# msp432-standard-feather.net
KiCad netlist of a schematic drawn in EAGLE
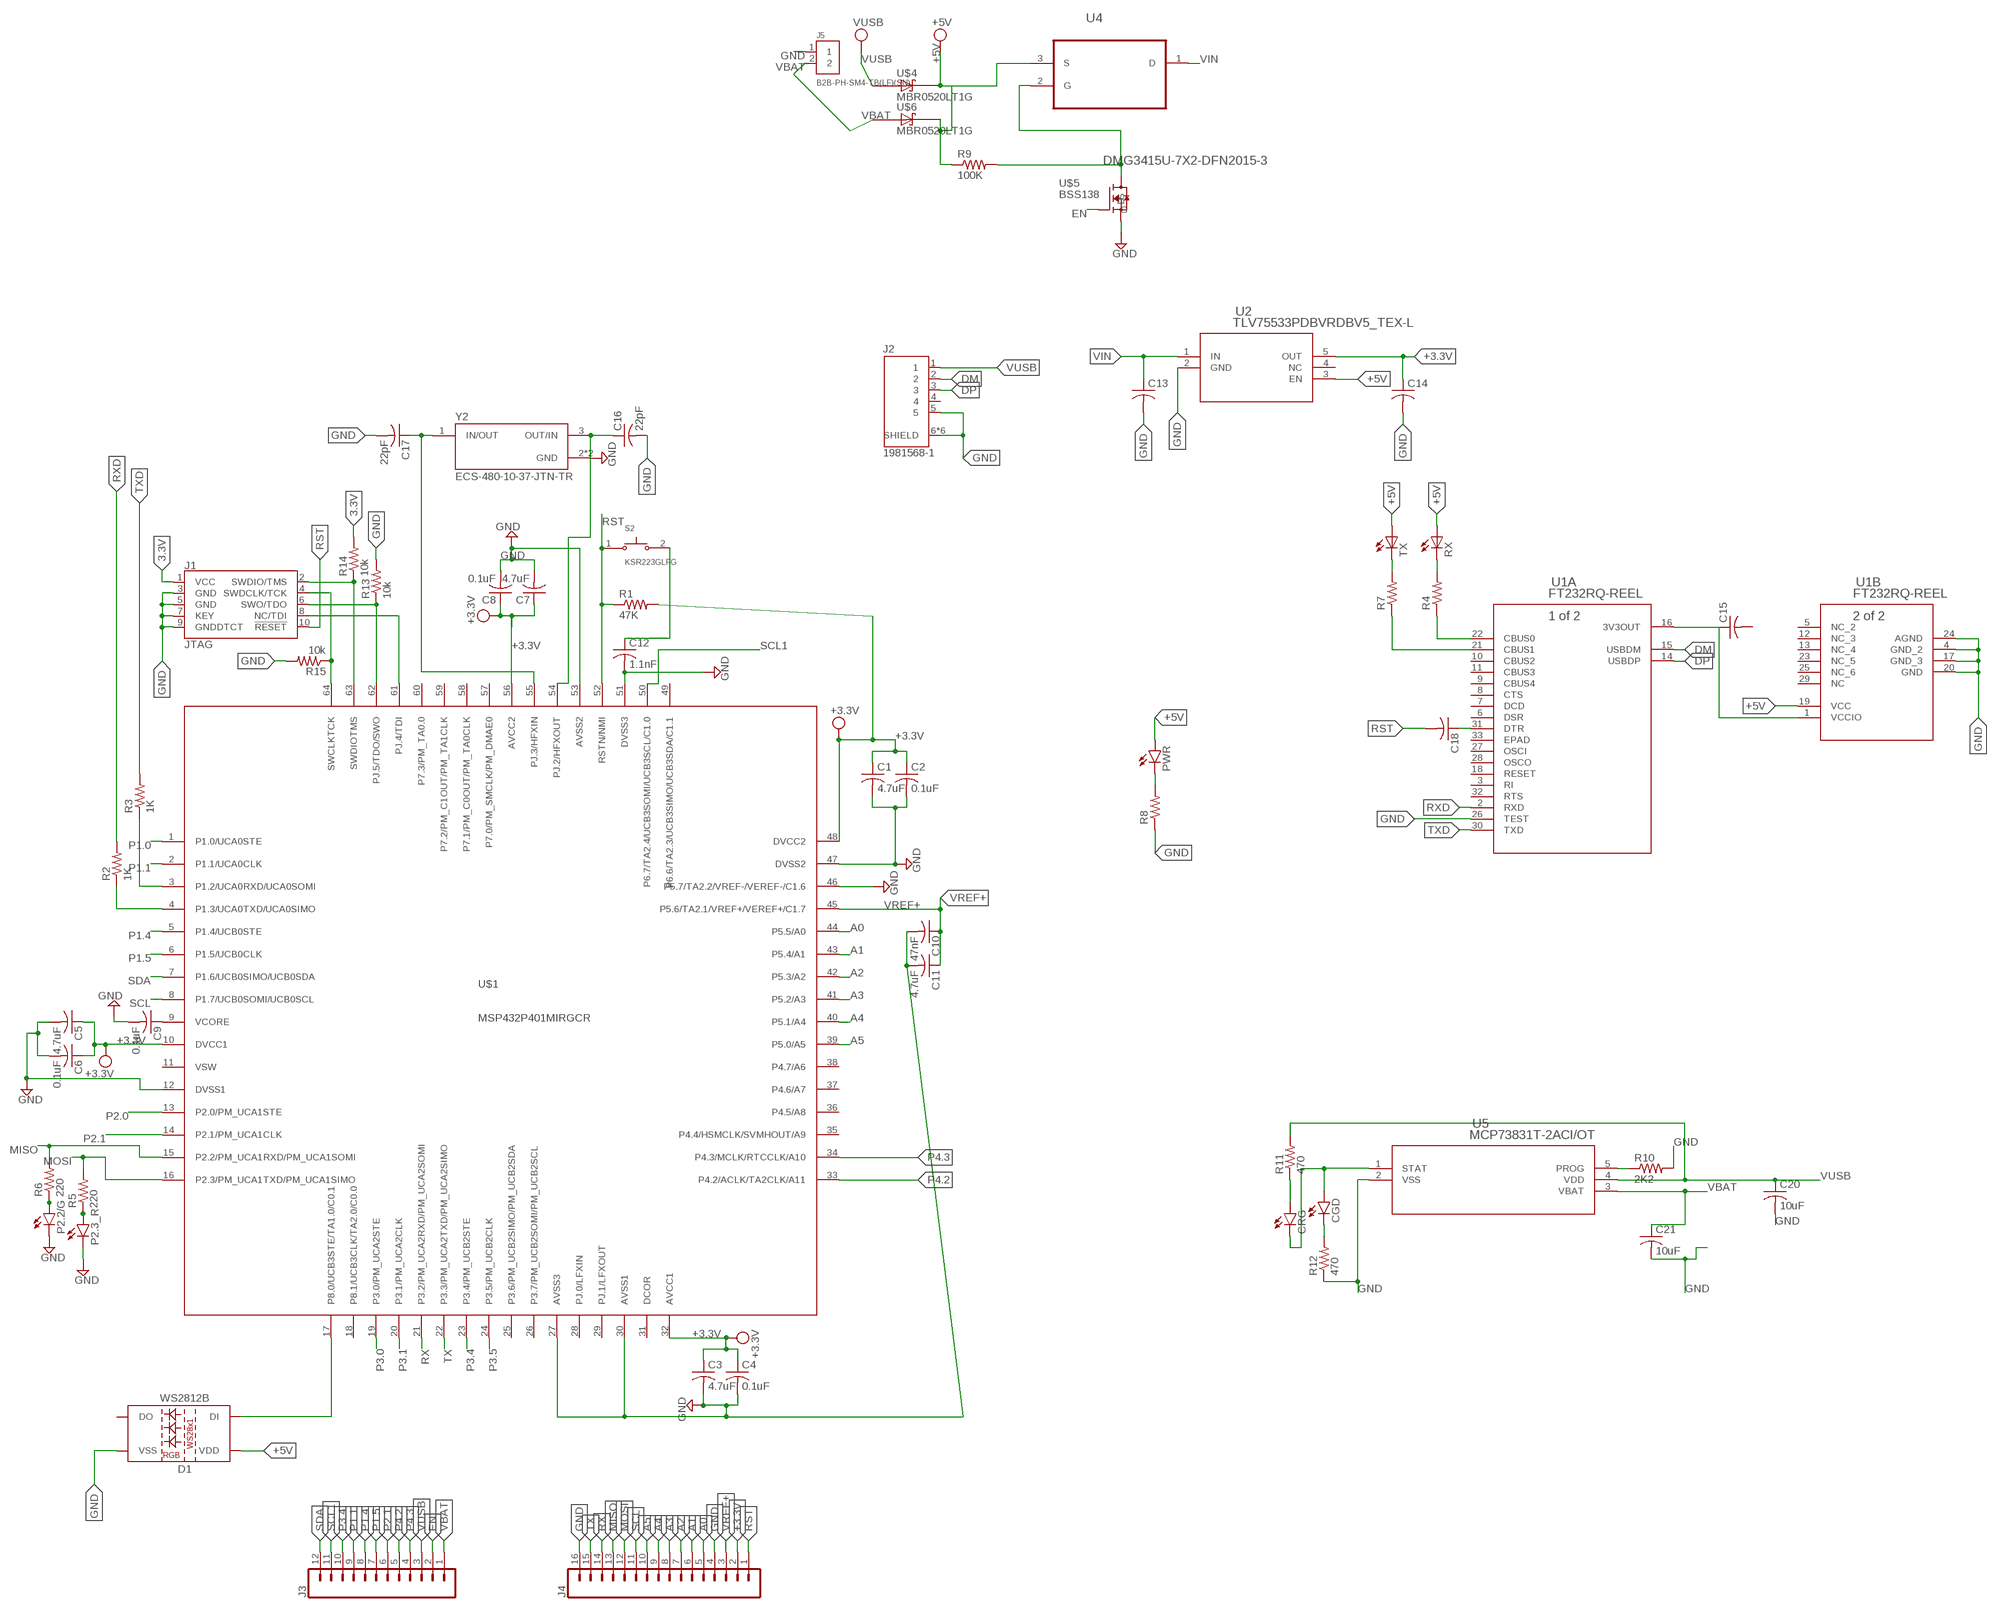
[diagram p0: schematic, sheet 1]

(export (version "E")
  (design (tool "Eeschema 10.0.6"))
  (components
    (comp (ref "C1")
      (value "4.7uF")
      (footprint "eagle-import:C0603")
      (libsource (lib "eagle-import") (part "C-USC0603"))
    )
    (comp (ref "C2")
      (value "0.1uF")
      (footprint "eagle-import:C0402")
      (libsource (lib "eagle-import") (part "C-USC0402"))
    )
    (comp (ref "C3")
      (value "4.7uF")
      (footprint "eagle-import:C0603")
      (libsource (lib "eagle-import") (part "C-USC0603"))
    )
    (comp (ref "C4")
      (value "0.1uF")
      (footprint "eagle-import:C0402")
      (libsource (lib "eagle-import") (part "C-USC0402"))
    )
    (comp (ref "C5")
      (value "4.7uF")
      (footprint "eagle-import:C0603")
      (libsource (lib "eagle-import") (part "C-USC0603"))
    )
    (comp (ref "C6")
      (value "0.1uF")
      (footprint "eagle-import:C0402")
      (libsource (lib "eagle-import") (part "C-USC0402"))
    )
    (comp (ref "C7")
      (value "4.7uF")
      (footprint "eagle-import:C0603")
      (libsource (lib "eagle-import") (part "C-USC0603"))
    )
    (comp (ref "C8")
      (value "0.1uF")
      (footprint "eagle-import:C0402")
      (libsource (lib "eagle-import") (part "C-USC0402"))
    )
    (comp (ref "C9")
      (value "0.1uF")
      (footprint "eagle-import:C0402")
      (libsource (lib "eagle-import") (part "C-USC0402"))
    )
    (comp (ref "C10")
      (value "47nF")
      (footprint "eagle-import:C0402")
      (libsource (lib "eagle-import") (part "C-USC0402"))
    )
    (comp (ref "C11")
      (value "4.7uF")
      (footprint "eagle-import:C0603")
      (libsource (lib "eagle-import") (part "C-USC0603"))
    )
    (comp (ref "C12")
      (value "1.1nF")
      (footprint "eagle-import:C0402")
      (libsource (lib "eagle-import") (part "C-USC0402"))
    )
    (comp (ref "C13")
      (value "C-USC0402")
      (footprint "eagle-import:C0402")
      (libsource (lib "eagle-import") (part "C-USC0402"))
    )
    (comp (ref "C14")
      (value "C-USC0402")
      (footprint "eagle-import:C0402")
      (libsource (lib "eagle-import") (part "C-USC0402"))
    )
    (comp (ref "C15")
      (value "C-USC0402")
      (footprint "eagle-import:C0402")
      (libsource (lib "eagle-import") (part "C-USC0402"))
    )
    (comp (ref "C16")
      (value "22pF")
      (footprint "eagle-import:C0402")
      (libsource (lib "eagle-import") (part "C-USC0402"))
    )
    (comp (ref "C17")
      (value "22pF")
      (footprint "eagle-import:C0402")
      (libsource (lib "eagle-import") (part "C-USC0402"))
    )
    (comp (ref "C18")
      (value "C-USC0402")
      (footprint "eagle-import:C0402")
      (libsource (lib "eagle-import") (part "C-USC0402"))
    )
    (comp (ref "C20")
      (value "10uF")
      (footprint "eagle-import:C0603")
      (libsource (lib "eagle-import") (part "C-USC0603"))
    )
    (comp (ref "C21")
      (value "10uF")
      (footprint "eagle-import:C0603")
      (libsource (lib "eagle-import") (part "C-USC0603"))
    )
    (comp (ref "CGD")
      (value "LEDCHIP-LED0603")
      (footprint "eagle-import:CHIP-LED0603")
      (libsource (lib "eagle-import") (part "led_259_LEDCHIP-LED0603"))
    )
    (comp (ref "CRG")
      (value "LEDCHIP-LED0603")
      (footprint "eagle-import:CHIP-LED0603")
      (libsource (lib "eagle-import") (part "led_259_LEDCHIP-LED0603"))
    )
    (comp (ref "D1")
      (value "WS2812B")
      (footprint "eagle-import:WS2812B")
      (libsource (lib "eagle-import") (part "WS2812B"))
    )
    (comp (ref "J1")
      (value "JTAG")
      (footprint "eagle-import:2X5-SMD-1.27MM")
      (libsource (lib "eagle-import") (part "CORTEX_JTAG_DEBUG_SMD"))
    )
    (comp (ref "J2")
      (value "1981568-1")
      (footprint "eagle-import:TE_1981568-1")
      (fields (field (name "MF") "TE Connectivity") (field (name "MP") "19815681"))
      (libsource (lib "eagle-import") (part "1981568-1"))
    )
    (comp (ref "J3")
      (value "CONN_12NO_SILK")
      (footprint "eagle-import:1X12_NO_SILK")
      (libsource (lib "eagle-import") (part "CONN_12NO_SILK"))
    )
    (comp (ref "J4")
      (value "CONN_161X16_NO_SILK")
      (footprint "eagle-import:1X16_NO_SILK")
      (libsource (lib "eagle-import") (part "CONN_161X16_NO_SILK"))
    )
    (comp (ref "J5")
      (value "B2B-PH-SM4-TB(LF)(SN)")
      (footprint "eagle-import:JST_B2B-PH-SM4-TB(LF)(SN)")
      (fields (field (name "MF") "JST Sales") (field (name "MP") "B2B-PH-SM4-TB_LF__SN_"))
      (libsource (lib "eagle-import") (part "B2B-PH-SM4-TB(LF)(SN)"))
    )
    (comp (ref "P2.2/G")
      (value "LEDCHIP-LED0603")
      (footprint "eagle-import:CHIP-LED0603")
      (libsource (lib "eagle-import") (part "led_259_LEDCHIP-LED0603"))
    )
    (comp (ref "P2.3_R")
      (value "LEDCHIP-LED0603")
      (footprint "eagle-import:CHIP-LED0603")
      (libsource (lib "eagle-import") (part "led_259_LEDCHIP-LED0603"))
    )
    (comp (ref "PWR")
      (value "LEDCHIP-LED0603")
      (footprint "eagle-import:CHIP-LED0603")
      (libsource (lib "eagle-import") (part "led_259_LEDCHIP-LED0603"))
    )
    (comp (ref "R1")
      (value "47K")
      (footprint "eagle-import:R0402")
      (libsource (lib "eagle-import") (part "R-US_R0402"))
    )
    (comp (ref "R2")
      (value "1K")
      (footprint "eagle-import:R0402")
      (libsource (lib "eagle-import") (part "R-US_R0402"))
    )
    (comp (ref "R3")
      (value "1K")
      (footprint "eagle-import:R0402")
      (libsource (lib "eagle-import") (part "R-US_R0402"))
    )
    (comp (ref "R4")
      (value "R-US_R0402")
      (footprint "eagle-import:R0402")
      (libsource (lib "eagle-import") (part "R-US_R0402"))
    )
    (comp (ref "R5")
      (value "220")
      (footprint "eagle-import:R0402")
      (libsource (lib "eagle-import") (part "R-US_R0402"))
    )
    (comp (ref "R6")
      (value "220")
      (footprint "eagle-import:R0402")
      (libsource (lib "eagle-import") (part "R-US_R0402"))
    )
    (comp (ref "R7")
      (value "R-US_R0402")
      (footprint "eagle-import:R0402")
      (libsource (lib "eagle-import") (part "R-US_R0402"))
    )
    (comp (ref "R8")
      (value "R-US_R0402")
      (footprint "eagle-import:R0402")
      (libsource (lib "eagle-import") (part "R-US_R0402"))
    )
    (comp (ref "R9")
      (value "100K")
      (footprint "eagle-import:R0402")
      (libsource (lib "eagle-import") (part "R-US_R0402"))
    )
    (comp (ref "R10")
      (value "2K2")
      (footprint "eagle-import:R0402")
      (libsource (lib "eagle-import") (part "R-US_R0402"))
    )
    (comp (ref "R11")
      (value "470")
      (footprint "eagle-import:R0402")
      (libsource (lib "eagle-import") (part "R-US_R0402"))
    )
    (comp (ref "R12")
      (value "470")
      (footprint "eagle-import:R0402")
      (libsource (lib "eagle-import") (part "R-US_R0402"))
    )
    (comp (ref "R13")
      (value "10k")
      (footprint "eagle-import:R0402")
      (libsource (lib "eagle-import") (part "R-US_R0402"))
    )
    (comp (ref "R14")
      (value "10k")
      (footprint "eagle-import:R0402")
      (libsource (lib "eagle-import") (part "R-US_R0402"))
    )
    (comp (ref "R15")
      (value "10k")
      (footprint "eagle-import:R0402")
      (libsource (lib "eagle-import") (part "R-US_R0402"))
    )
    (comp (ref "RX")
      (value "LEDCHIP-LED0603")
      (footprint "eagle-import:CHIP-LED0603")
      (libsource (lib "eagle-import") (part "LEDCHIP-LED0603"))
    )
    (comp (ref "S2")
      (value "KSR223GLFG")
      (footprint "eagle-import:SW_KSR223GLFG")
      (fields (field (name "MF") "C&K"))
      (libsource (lib "eagle-import") (part "KSR223GLFG"))
    )
    (comp (ref "TX")
      (value "LEDCHIP-LED0603")
      (footprint "eagle-import:CHIP-LED0603")
      (libsource (lib "eagle-import") (part "LEDCHIP-LED0603"))
    )
    (comp (ref "U$1")
      (value "MSP432P401MIRGCR")
      (footprint "eagle-import:MSP432_QFN_64")
      (fields (field (name "MF") "Texas Instruments"))
      (libsource (lib "eagle-import") (part "MSP432P401MIRGCR"))
    )
    (comp (ref "U$4")
      (value "MBR0520LT1G")
      (footprint "eagle-import:SOD3716X117(SOD-123)")
      (fields (field (name "MF") "ON Semiconductor"))
      (libsource (lib "eagle-import") (part "MBR0520LT1G"))
    )
    (comp (ref "U$5")
      (value "BSS138")
      (footprint "eagle-import:BSS138")
      (fields (field (name "MF") "MICROSS/On Semiconductor"))
      (libsource (lib "eagle-import") (part "BSS138"))
    )
    (comp (ref "U$6")
      (value "MBR0520LT1G")
      (footprint "eagle-import:SOD3716X117(SOD-123)")
      (fields (field (name "MF") "ON Semiconductor"))
      (libsource (lib "eagle-import") (part "MBR0520LT1G"))
    )
    (comp (ref "U1")
      (value "FT232RQ-REEL")
      (footprint "eagle-import:FT232RQ-REEL_FTD")
      (fields (field (name "COPYRIGHT") "Copyright (C) 2018 Accelerated Designs. All rights reserved"))
      (libsource (lib "eagle-import") (part "FT232RQ-REEL"))
    )
    (comp (ref "U2")
      (value "TLV75533PDBVRDBV5_TEX-L")
      (footprint "eagle-import:DBV5_TEX-L")
      (fields
        (field (name "MANUFACTURER_PART_NUMBER") "TLV75533PDBVR")
        (field (name "COPYRIGHT") "Copyright (C) 2018 Accelerated Designs. All rights reserved")
      )
      (libsource (lib "eagle-import") (part "TLV75533PDBVRDBV5_TEX-L"))
    )
    (comp (ref "U4")
      (value "DMG3415U-7X2-DFN2015-3")
      (footprint "eagle-import:X2-DFN2015-3")
      (libsource (lib "eagle-import") (part "DMG3415U-7X2-DFN2015-3"))
    )
    (comp (ref "U5")
      (value "MCP73831T-2ACI/OT")
      (footprint "eagle-import:SOT-23-5_MC")
      (libsource (lib "eagle-import") (part "MCP73831T-2ACI/OT"))
    )
    (comp (ref "Y2")
      (value "ECS-480-10-37-JTN-TR")
      (footprint "eagle-import:XTAL_ECS-480-10-37-JTN-TR")
      (fields (field (name "MF") "ECS Inc."))
      (libsource (lib "eagle-import") (part "ECS-480-10-37-JTN-TR"))
    )
  )
  (nets
    (net (code "1") (name "+3.3V") (class "Default")
      (node (ref "C1") (pin "1") (pinfunction "1_1") (pintype "passive"))
      (node (ref "C14") (pin "1") (pinfunction "1_1") (pintype "passive"))
      (node (ref "C2") (pin "1") (pinfunction "1_1") (pintype "passive"))
      (node (ref "C3") (pin "1") (pinfunction "1_1") (pintype "passive"))
      (node (ref "C4") (pin "1") (pinfunction "1_1") (pintype "passive"))
      (node (ref "C5") (pin "1") (pinfunction "1_1") (pintype "passive"))
      (node (ref "C6") (pin "1") (pinfunction "1_1") (pintype "passive"))
      (node (ref "C7") (pin "1") (pinfunction "1_1") (pintype "passive"))
      (node (ref "C8") (pin "1") (pinfunction "1_1") (pintype "passive"))
      (node (ref "J4") (pin "2") (pinfunction "2_2") (pintype "passive"))
      (node (ref "R1") (pin "2") (pinfunction "2_2") (pintype "passive"))
      (node (ref "U$1") (pin "10") (pinfunction "DVCC1_10") (pintype "bidirectional"))
      (node (ref "U$1") (pin "32") (pinfunction "AVCC1_32") (pintype "bidirectional"))
      (node (ref "U$1") (pin "48") (pinfunction "DVCC2_48") (pintype "bidirectional"))
      (node (ref "U$1") (pin "56") (pinfunction "AVCC2_56") (pintype "bidirectional"))
      (node (ref "U2") (pin "5") (pinfunction "OUT_5") (pintype "output"))
    )
    (net (code "2") (name "+5V") (class "Default")
      (node (ref "D1") (pin "1") (pinfunction "VDD_1") (pintype "bidirectional"))
      (node (ref "PWR") (pin "A") (pinfunction "A_A") (pintype "passive"))
      (node (ref "R9") (pin "1") (pinfunction "1_1") (pintype "passive"))
      (node (ref "RX") (pin "A") (pinfunction "A_A") (pintype "passive"))
      (node (ref "TX") (pin "A") (pinfunction "A_A") (pintype "passive"))
      (node (ref "U$4") (pin "1") (pinfunction "C_1") (pintype "passive"))
      (node (ref "U$6") (pin "1") (pinfunction "C_1") (pintype "passive"))
      (node (ref "U1") (pin "19") (pinfunction "VCC_19") (pintype "passive"))
      (node (ref "U2") (pin "3") (pinfunction "EN_3") (pintype "input"))
      (node (ref "U4") (pin "3") (pinfunction "S_3") (pintype "passive"))
    )
    (net (code "3") (name "/P1.0") (class "Default")
      (node (ref "U$1") (pin "1") (pinfunction "P1.0/UCA0STE_1") (pintype "bidirectional"))
    )
    (net (code "4") (name "/P2.0") (class "Default")
      (node (ref "U$1") (pin "13") (pinfunction "P2.0/PM_UCA1STE_13") (pintype "bidirectional"))
    )
    (net (code "5") (name "/P3.0") (class "Default")
      (node (ref "U$1") (pin "19") (pinfunction "P3.0/PM_UCA2STE_19") (pintype "bidirectional"))
    )
    (net (code "6") (name "/P3.1") (class "Default")
      (node (ref "U$1") (pin "20") (pinfunction "P3.1/PM_UCA2CLK_20") (pintype "bidirectional"))
    )
    (net (code "7") (name "/P3.5") (class "Default")
      (node (ref "U$1") (pin "24") (pinfunction "P3.5/PM_UCB2CLK_24") (pintype "bidirectional"))
    )
    (net (code "8") (name "3.3V") (class "Default")
      (node (ref "J1") (pin "1") (pinfunction "VCC_1") (pintype "bidirectional"))
      (node (ref "R14") (pin "2") (pinfunction "2_2") (pintype "passive"))
    )
    (net (code "9") (name "A0") (class "Default")
      (node (ref "J4") (pin "5") (pinfunction "5_5") (pintype "passive"))
      (node (ref "U$1") (pin "44") (pinfunction "P5.5/A0_44") (pintype "bidirectional"))
    )
    (net (code "10") (name "A1") (class "Default")
      (node (ref "J4") (pin "6") (pinfunction "6_6") (pintype "passive"))
      (node (ref "U$1") (pin "43") (pinfunction "P5.4/A1_43") (pintype "bidirectional"))
    )
    (net (code "11") (name "A2") (class "Default")
      (node (ref "J4") (pin "7") (pinfunction "7_7") (pintype "passive"))
      (node (ref "U$1") (pin "42") (pinfunction "P5.3/A2_42") (pintype "bidirectional"))
    )
    (net (code "12") (name "A3") (class "Default")
      (node (ref "J4") (pin "8") (pinfunction "8_8") (pintype "passive"))
      (node (ref "U$1") (pin "41") (pinfunction "P5.2/A3_41") (pintype "bidirectional"))
    )
    (net (code "13") (name "A4") (class "Default")
      (node (ref "J4") (pin "9") (pinfunction "9_9") (pintype "passive"))
      (node (ref "U$1") (pin "40") (pinfunction "P5.1/A4_40") (pintype "bidirectional"))
    )
    (net (code "14") (name "A5") (class "Default")
      (node (ref "J4") (pin "10") (pinfunction "10_10") (pintype "passive"))
      (node (ref "U$1") (pin "39") (pinfunction "P5.0/A5_39") (pintype "bidirectional"))
    )
    (net (code "15") (name "DM") (class "Default")
      (node (ref "J2") (pin "2") (pinfunction "2_2") (pintype "passive"))
      (node (ref "U1") (pin "15") (pinfunction "USBDM_15") (pintype "passive"))
    )
    (net (code "16") (name "DP") (class "Default")
      (node (ref "J2") (pin "3") (pinfunction "3_3") (pintype "passive"))
      (node (ref "U1") (pin "14") (pinfunction "USBDP_14") (pintype "passive"))
    )
    (net (code "17") (name "EN") (class "Default")
      (node (ref "J3") (pin "2") (pinfunction "2_2") (pintype "passive"))
      (node (ref "U$5") (pin "G") (pinfunction "G_G") (pintype "passive"))
    )
    (net (code "18") (name "GND") (class "Default")
      (node (ref "C1") (pin "2") (pinfunction "2_2") (pintype "passive"))
      (node (ref "C10") (pin "2") (pinfunction "2_2") (pintype "passive"))
      (node (ref "C11") (pin "2") (pinfunction "2_2") (pintype "passive"))
      (node (ref "C12") (pin "2") (pinfunction "2_2") (pintype "passive"))
      (node (ref "C13") (pin "2") (pinfunction "2_2") (pintype "passive"))
      (node (ref "C14") (pin "2") (pinfunction "2_2") (pintype "passive"))
      (node (ref "C16") (pin "2") (pinfunction "2_2") (pintype "passive"))
      (node (ref "C17") (pin "2") (pinfunction "2_2") (pintype "passive"))
      (node (ref "C2") (pin "2") (pinfunction "2_2") (pintype "passive"))
      (node (ref "C20") (pin "2") (pinfunction "2_2") (pintype "passive"))
      (node (ref "C21") (pin "2") (pinfunction "2_2") (pintype "passive"))
      (node (ref "C3") (pin "2") (pinfunction "2_2") (pintype "passive"))
      (node (ref "C4") (pin "2") (pinfunction "2_2") (pintype "passive"))
      (node (ref "C5") (pin "2") (pinfunction "2_2") (pintype "passive"))
      (node (ref "C6") (pin "2") (pinfunction "2_2") (pintype "passive"))
      (node (ref "C7") (pin "2") (pinfunction "2_2") (pintype "passive"))
      (node (ref "C8") (pin "2") (pinfunction "2_2") (pintype "passive"))
      (node (ref "C9") (pin "2") (pinfunction "2_2") (pintype "passive"))
      (node (ref "D1") (pin "3") (pinfunction "VSS_3") (pintype "bidirectional"))
      (node (ref "J1") (pin "3") (pinfunction "GND_3") (pintype "bidirectional"))
      (node (ref "J1") (pin "5") (pinfunction "GND_5") (pintype "bidirectional"))
      (node (ref "J1") (pin "7") (pinfunction "KEY_7") (pintype "bidirectional"))
      (node (ref "J1") (pin "9") (pinfunction "GNDDTCT_9") (pintype "bidirectional"))
      (node (ref "J2") (pin "10") (pinfunction "SHIELD_10") (pintype "passive"))
      (node (ref "J2") (pin "11") (pinfunction "SHIELD_11") (pintype "passive"))
      (node (ref "J2") (pin "5") (pinfunction "5_5") (pintype "passive"))
      (node (ref "J2") (pin "6") (pinfunction "SHIELD_6") (pintype "passive"))
      (node (ref "J2") (pin "7") (pinfunction "SHIELD_7") (pintype "passive"))
      (node (ref "J2") (pin "8") (pinfunction "SHIELD_8") (pintype "passive"))
      (node (ref "J2") (pin "9") (pinfunction "SHIELD_9") (pintype "passive"))
      (node (ref "J4") (pin "16") (pinfunction "16_16") (pintype "passive"))
      (node (ref "J4") (pin "4") (pinfunction "4_4") (pintype "passive"))
      (node (ref "J5") (pin "1") (pinfunction "1_1") (pintype "passive"))
      (node (ref "P2.2/G") (pin "C") (pinfunction "C_C") (pintype "passive"))
      (node (ref "P2.3_R") (pin "C") (pinfunction "C_C") (pintype "passive"))
      (node (ref "R10") (pin "2") (pinfunction "2_2") (pintype "passive"))
      (node (ref "R12") (pin "1") (pinfunction "1_1") (pintype "passive"))
      (node (ref "R13") (pin "2") (pinfunction "2_2") (pintype "passive"))
      (node (ref "R15") (pin "2") (pinfunction "2_2") (pintype "passive"))
      (node (ref "R8") (pin "1") (pinfunction "1_1") (pintype "passive"))
      (node (ref "U$1") (pin "12") (pinfunction "DVSS1_12") (pintype "bidirectional"))
      (node (ref "U$1") (pin "27") (pinfunction "AVSS3_27") (pintype "bidirectional"))
      (node (ref "U$1") (pin "30") (pinfunction "AVSS1_30") (pintype "bidirectional"))
      (node (ref "U$1") (pin "46") (pinfunction "P5.7/TA2.2/VREF-/VEREF-/C1.6_46") (pintype "bidirectional"))
      (node (ref "U$1") (pin "47") (pinfunction "DVSS2_47") (pintype "bidirectional"))
      (node (ref "U$1") (pin "51") (pinfunction "DVSS3_51") (pintype "bidirectional"))
      (node (ref "U$1") (pin "53") (pinfunction "AVSS2_53") (pintype "bidirectional"))
      (node (ref "U$5") (pin "S") (pinfunction "S_S") (pintype "passive"))
      (node (ref "U1") (pin "17") (pinfunction "GND_3_17") (pintype "passive"))
      (node (ref "U1") (pin "20") (pinfunction "GND_20") (pintype "passive"))
      (node (ref "U1") (pin "24") (pinfunction "AGND_24") (pintype "passive"))
      (node (ref "U1") (pin "26") (pinfunction "TEST_26") (pintype "passive"))
      (node (ref "U1") (pin "4") (pinfunction "GND_2_4") (pintype "passive"))
      (node (ref "U2") (pin "2") (pinfunction "GND_2") (pintype "power_in"))
      (node (ref "U5") (pin "2") (pinfunction "VSS_2") (pintype "passive"))
      (node (ref "Y2") (pin "2") (pinfunction "GND_2") (pintype "power_in"))
      (node (ref "Y2") (pin "4") (pinfunction "GND_4") (pintype "power_in"))
    )
    (net (code "19") (name "MISO") (class "Default")
      (node (ref "J4") (pin "13") (pinfunction "13_13") (pintype "passive"))
      (node (ref "R6") (pin "2") (pinfunction "2_2") (pintype "passive"))
      (node (ref "U$1") (pin "15") (pinfunction "P2.2/PM_UCA1RXD/PM_UCA1SOMI_15") (pintype "bidirectional"))
    )
    (net (code "20") (name "MOSI") (class "Default")
      (node (ref "J4") (pin "12") (pinfunction "12_12") (pintype "passive"))
      (node (ref "R5") (pin "2") (pinfunction "2_2") (pintype "passive"))
      (node (ref "U$1") (pin "16") (pinfunction "P2.3/PM_UCA1TXD/PM_UCA1SIMO_16") (pintype "bidirectional"))
    )
    (net (code "21") (name "Net-(C12-Pad1)") (class "Default")
      (node (ref "C12") (pin "1") (pinfunction "1_1") (pintype "passive"))
      (node (ref "S2") (pin "2") (pinfunction "2_2") (pintype "passive"))
    )
    (net (code "22") (name "Net-(CGD-PadC)") (class "Default")
      (node (ref "CGD") (pin "C") (pinfunction "C_C") (pintype "passive"))
      (node (ref "R12") (pin "2") (pinfunction "2_2") (pintype "passive"))
    )
    (net (code "23") (name "Net-(CRG-PadA)") (class "Default")
      (node (ref "CRG") (pin "A") (pinfunction "A_A") (pintype "passive"))
      (node (ref "R11") (pin "1") (pinfunction "1_1") (pintype "passive"))
    )
    (net (code "24") (name "Net-(D1-DI)") (class "Default")
      (node (ref "D1") (pin "4") (pinfunction "DI_4") (pintype "bidirectional"))
      (node (ref "U$1") (pin "17") (pinfunction "P8.0/UCB3STE/TA1.0/C0.1_17") (pintype "bidirectional"))
    )
    (net (code "25") (name "Net-(J1-NC{slash}TDI)") (class "Default")
      (node (ref "J1") (pin "8") (pinfunction "NC/TDI_8") (pintype "bidirectional"))
      (node (ref "U$1") (pin "61") (pinfunction "PJ.4/TDI_61") (pintype "bidirectional"))
    )
    (net (code "26") (name "Net-(J1-SWDCLK{slash}TCK)") (class "Default")
      (node (ref "J1") (pin "4") (pinfunction "SWDCLK/TCK_4") (pintype "bidirectional"))
      (node (ref "R15") (pin "1") (pinfunction "1_1") (pintype "passive"))
      (node (ref "U$1") (pin "64") (pinfunction "SWCLKTCK_64") (pintype "bidirectional"))
    )
    (net (code "27") (name "Net-(J1-SWDIO{slash}TMS)") (class "Default")
      (node (ref "J1") (pin "2") (pinfunction "SWDIO/TMS_2") (pintype "bidirectional"))
      (node (ref "R14") (pin "1") (pinfunction "1_1") (pintype "passive"))
      (node (ref "U$1") (pin "63") (pinfunction "SWDIOTMS_63") (pintype "bidirectional"))
    )
    (net (code "28") (name "Net-(J1-SWO{slash}TDO)") (class "Default")
      (node (ref "J1") (pin "6") (pinfunction "SWO/TDO_6") (pintype "bidirectional"))
      (node (ref "R13") (pin "1") (pinfunction "1_1") (pintype "passive"))
      (node (ref "U$1") (pin "62") (pinfunction "PJ.5/TDO/SWO_62") (pintype "bidirectional"))
    )
    (net (code "29") (name "Net-(P2.2/G-PadA)") (class "Default")
      (node (ref "P2.2/G") (pin "A") (pinfunction "A_A") (pintype "passive"))
      (node (ref "R6") (pin "1") (pinfunction "1_1") (pintype "passive"))
    )
    (net (code "30") (name "Net-(P2.3_R-PadA)") (class "Default")
      (node (ref "P2.3_R") (pin "A") (pinfunction "A_A") (pintype "passive"))
      (node (ref "R5") (pin "1") (pinfunction "1_1") (pintype "passive"))
    )
    (net (code "31") (name "Net-(PWR-PadC)") (class "Default")
      (node (ref "PWR") (pin "C") (pinfunction "C_C") (pintype "passive"))
      (node (ref "R8") (pin "2") (pinfunction "2_2") (pintype "passive"))
    )
    (net (code "32") (name "Net-(R4-Pad2)") (class "Default")
      (node (ref "R4") (pin "2") (pinfunction "2_2") (pintype "passive"))
      (node (ref "RX") (pin "C") (pinfunction "C_C") (pintype "passive"))
    )
    (net (code "33") (name "Net-(R7-Pad2)") (class "Default")
      (node (ref "R7") (pin "2") (pinfunction "2_2") (pintype "passive"))
      (node (ref "TX") (pin "C") (pinfunction "C_C") (pintype "passive"))
    )
    (net (code "34") (name "Net-(U$1-P1.2{slash}UCA0RXD{slash}UCA0SOMI)") (class "Default")
      (node (ref "R3") (pin "1") (pinfunction "1_1") (pintype "passive"))
      (node (ref "U$1") (pin "3") (pinfunction "P1.2/UCA0RXD/UCA0SOMI_3") (pintype "bidirectional"))
    )
    (net (code "35") (name "Net-(U$1-P1.3{slash}UCA0TXD{slash}UCA0SIMO)") (class "Default")
      (node (ref "R2") (pin "1") (pinfunction "1_1") (pintype "passive"))
      (node (ref "U$1") (pin "4") (pinfunction "P1.3/UCA0TXD/UCA0SIMO_4") (pintype "bidirectional"))
    )
    (net (code "36") (name "Net-(U$1-PJ.2{slash}HFXOUT)") (class "Default")
      (node (ref "C16") (pin "1") (pinfunction "1_1") (pintype "passive"))
      (node (ref "U$1") (pin "54") (pinfunction "PJ.2/HFXOUT_54") (pintype "bidirectional"))
      (node (ref "Y2") (pin "3") (pinfunction "OUT/IN_3") (pintype "bidirectional"))
    )
    (net (code "37") (name "Net-(U$1-PJ.3{slash}HFXIN)") (class "Default")
      (node (ref "C17") (pin "1") (pinfunction "1_1") (pintype "passive"))
      (node (ref "U$1") (pin "55") (pinfunction "PJ.3/HFXIN_55") (pintype "bidirectional"))
      (node (ref "Y2") (pin "1") (pinfunction "IN/OUT_1") (pintype "bidirectional"))
    )
    (net (code "38") (name "Net-(U$1-VCORE)") (class "Default")
      (node (ref "C9") (pin "1") (pinfunction "1_1") (pintype "passive"))
      (node (ref "U$1") (pin "9") (pinfunction "VCORE_9") (pintype "bidirectional"))
    )
    (net (code "39") (name "Net-(U1A-3V3OUT)") (class "Default")
      (node (ref "C15") (pin "1") (pinfunction "1_1") (pintype "passive"))
      (node (ref "U1") (pin "1") (pinfunction "VCCIO_1") (pintype "passive"))
      (node (ref "U1") (pin "16") (pinfunction "3V3OUT_16") (pintype "passive"))
    )
    (net (code "40") (name "Net-(U1A-CBUS0)") (class "Default")
      (node (ref "R4") (pin "1") (pinfunction "1_1") (pintype "passive"))
      (node (ref "U1") (pin "22") (pinfunction "CBUS0_22") (pintype "passive"))
    )
    (net (code "41") (name "Net-(U1A-CBUS1)") (class "Default")
      (node (ref "R7") (pin "1") (pinfunction "1_1") (pintype "passive"))
      (node (ref "U1") (pin "21") (pinfunction "CBUS1_21") (pintype "passive"))
    )
    (net (code "42") (name "Net-(U1A-DTR)") (class "Default")
      (node (ref "C18") (pin "1") (pinfunction "1_1") (pintype "passive"))
      (node (ref "U1") (pin "31") (pinfunction "DTR_31") (pintype "passive"))
    )
    (net (code "43") (name "Net-(U4-G)") (class "Default")
      (node (ref "R9") (pin "2") (pinfunction "2_2") (pintype "passive"))
      (node (ref "U$5") (pin "D") (pinfunction "D_D") (pintype "passive"))
      (node (ref "U4") (pin "2") (pinfunction "G_2") (pintype "power_in"))
    )
    (net (code "44") (name "Net-(U5-PROG)") (class "Default")
      (node (ref "R10") (pin "1") (pinfunction "1_1") (pintype "passive"))
      (node (ref "U5") (pin "5") (pinfunction "PROG_5") (pintype "passive"))
    )
    (net (code "45") (name "Net-(U5-STAT)") (class "Default")
      (node (ref "CGD") (pin "A") (pinfunction "A_A") (pintype "passive"))
      (node (ref "CRG") (pin "C") (pinfunction "C_C") (pintype "passive"))
      (node (ref "U5") (pin "1") (pinfunction "STAT_1") (pintype "passive"))
    )
    (net (code "46") (name "P1.1") (class "Default")
      (node (ref "J3") (pin "9") (pinfunction "9_9") (pintype "passive"))
      (node (ref "U$1") (pin "2") (pinfunction "P1.1/UCA0CLK_2") (pintype "bidirectional"))
    )
    (net (code "47") (name "P1.4") (class "Default")
      (node (ref "J3") (pin "8") (pinfunction "8_8") (pintype "passive"))
      (node (ref "U$1") (pin "5") (pinfunction "P1.4/UCB0STE_5") (pintype "bidirectional"))
    )
    (net (code "48") (name "P1.5") (class "Default")
      (node (ref "J3") (pin "7") (pinfunction "7_7") (pintype "passive"))
      (node (ref "U$1") (pin "6") (pinfunction "P1.5/UCB0CLK_6") (pintype "bidirectional"))
    )
    (net (code "49") (name "P2.1") (class "Default")
      (node (ref "J3") (pin "6") (pinfunction "6_6") (pintype "passive"))
      (node (ref "U$1") (pin "14") (pinfunction "P2.1/PM_UCA1CLK_14") (pintype "bidirectional"))
    )
    (net (code "50") (name "P3.4") (class "Default")
      (node (ref "J3") (pin "10") (pinfunction "10_10") (pintype "passive"))
      (node (ref "U$1") (pin "23") (pinfunction "P3.4/PM_UCB2STE_23") (pintype "bidirectional"))
    )
    (net (code "51") (name "P4.2") (class "Default")
      (node (ref "J3") (pin "5") (pinfunction "5_5") (pintype "passive"))
      (node (ref "U$1") (pin "33") (pinfunction "P4.2/ACLK/TA2CLK/A11_33") (pintype "bidirectional"))
    )
    (net (code "52") (name "P4.3") (class "Default")
      (node (ref "J3") (pin "4") (pinfunction "4_4") (pintype "passive"))
      (node (ref "U$1") (pin "34") (pinfunction "P4.3/MCLK/RTCCLK/A10_34") (pintype "bidirectional"))
    )
    (net (code "53") (name "RST") (class "Default")
      (node (ref "C18") (pin "2") (pinfunction "2_2") (pintype "passive"))
      (node (ref "J1") (pin "10") (pinfunction "~{RESET}_10") (pintype "bidirectional"))
      (node (ref "J4") (pin "1") (pinfunction "1_1") (pintype "passive"))
      (node (ref "R1") (pin "1") (pinfunction "1_1") (pintype "passive"))
      (node (ref "S2") (pin "1") (pinfunction "1_1") (pintype "passive"))
      (node (ref "U$1") (pin "52") (pinfunction "RSTN/NMI_52") (pintype "bidirectional"))
    )
    (net (code "54") (name "RX") (class "Default")
      (node (ref "J4") (pin "14") (pinfunction "14_14") (pintype "passive"))
      (node (ref "U$1") (pin "21") (pinfunction "P3.2/PM_UCA2RXD/PM_UCA2SOMI_21") (pintype "bidirectional"))
    )
    (net (code "55") (name "RXD") (class "Default")
      (node (ref "R2") (pin "2") (pinfunction "2_2") (pintype "passive"))
      (node (ref "U1") (pin "2") (pinfunction "RXD_2") (pintype "passive"))
    )
    (net (code "56") (name "SCL") (class "Default")
      (node (ref "J4") (pin "11") (pinfunction "11_11") (pintype "passive"))
      (node (ref "U$1") (pin "8") (pinfunction "P1.7/UCB0SOMI/UCB0SCL_8") (pintype "bidirectional"))
    )
    (net (code "57") (name "SCL1") (class "Default")
      (node (ref "J3") (pin "11") (pinfunction "11_11") (pintype "passive"))
      (node (ref "U$1") (pin "50") (pinfunction "P6.7/TA2.4/UCB3SOMI/UCB3SCL/C1.0_50") (pintype "bidirectional"))
    )
    (net (code "58") (name "SDA") (class "Default")
      (node (ref "J3") (pin "12") (pinfunction "12_12") (pintype "passive"))
      (node (ref "U$1") (pin "7") (pinfunction "P1.6/UCB0SIMO/UCB0SDA_7") (pintype "bidirectional"))
    )
    (net (code "59") (name "TX") (class "Default")
      (node (ref "J4") (pin "15") (pinfunction "15_15") (pintype "passive"))
      (node (ref "U$1") (pin "22") (pinfunction "P3.3/PM_UCA2TXD/PM_UCA2SIMO_22") (pintype "bidirectional"))
    )
    (net (code "60") (name "TXD") (class "Default")
      (node (ref "R3") (pin "2") (pinfunction "2_2") (pintype "passive"))
      (node (ref "U1") (pin "30") (pinfunction "TXD_30") (pintype "passive"))
    )
    (net (code "61") (name "VBAT") (class "Default")
      (node (ref "C21") (pin "1") (pinfunction "1_1") (pintype "passive"))
      (node (ref "J3") (pin "1") (pinfunction "1_1") (pintype "passive"))
      (node (ref "J5") (pin "2") (pinfunction "2_2") (pintype "passive"))
      (node (ref "U$6") (pin "2") (pinfunction "A_2") (pintype "passive"))
      (node (ref "U5") (pin "3") (pinfunction "VBAT_3") (pintype "passive"))
    )
    (net (code "62") (name "VIN") (class "Default")
      (node (ref "C13") (pin "1") (pinfunction "1_1") (pintype "passive"))
      (node (ref "U2") (pin "1") (pinfunction "IN_1") (pintype "input"))
      (node (ref "U4") (pin "1") (pinfunction "D_1") (pintype "output"))
    )
    (net (code "63") (name "VREF+") (class "Default")
      (node (ref "C10") (pin "1") (pinfunction "1_1") (pintype "passive"))
      (node (ref "C11") (pin "1") (pinfunction "1_1") (pintype "passive"))
      (node (ref "J4") (pin "3") (pinfunction "3_3") (pintype "passive"))
      (node (ref "U$1") (pin "45") (pinfunction "P5.6/TA2.1/VREF+/VEREF+/C1.7_45") (pintype "bidirectional"))
    )
    (net (code "64") (name "VUSB") (class "Default")
      (node (ref "C20") (pin "1") (pinfunction "1_1") (pintype "passive"))
      (node (ref "J2") (pin "1") (pinfunction "1_1") (pintype "passive"))
      (node (ref "J3") (pin "3") (pinfunction "3_3") (pintype "passive"))
      (node (ref "R11") (pin "2") (pinfunction "2_2") (pintype "passive"))
      (node (ref "U$4") (pin "2") (pinfunction "A_2") (pintype "passive"))
      (node (ref "U5") (pin "4") (pinfunction "VDD_4") (pintype "passive"))
    )
    (net (code "65") (name "unconnected-(C15-Pad2)") (class "Default")
      (node (ref "C15") (pin "2") (pinfunction "2_2") (pintype "passive"))
    )
    (net (code "66") (name "unconnected-(D1-DO-Pad2)") (class "Default")
      (node (ref "D1") (pin "2") (pinfunction "DO_2") (pintype "bidirectional"))
    )
    (net (code "67") (name "unconnected-(J2-Pad4)") (class "Default")
      (node (ref "J2") (pin "4") (pinfunction "4_4") (pintype "passive"))
    )
    (net (code "68") (name "unconnected-(U$1-DCOR-Pad31)") (class "Default")
      (node (ref "U$1") (pin "31") (pinfunction "DCOR_31") (pintype "bidirectional"))
    )
    (net (code "69") (name "unconnected-(U$1-P3.6{slash}PM_UCB2SIMO{slash}PM_UCB2SDA-Pad25)") (class "Default")
      (node (ref "U$1") (pin "25") (pinfunction "P3.6/PM_UCB2SIMO/PM_UCB2SDA_25") (pintype "bidirectional"))
    )
    (net (code "70") (name "unconnected-(U$1-P3.7{slash}PM_UCB2SOMI{slash}PM_UCB2SCL-Pad26)") (class "Default")
      (node (ref "U$1") (pin "26") (pinfunction "P3.7/PM_UCB2SOMI/PM_UCB2SCL_26") (pintype "bidirectional"))
    )
    (net (code "71") (name "unconnected-(U$1-P4.4{slash}HSMCLK{slash}SVMHOUT{slash}A9-Pad35)") (class "Default")
      (node (ref "U$1") (pin "35") (pinfunction "P4.4/HSMCLK/SVMHOUT/A9_35") (pintype "bidirectional"))
    )
    (net (code "72") (name "unconnected-(U$1-P4.5{slash}A8-Pad36)") (class "Default")
      (node (ref "U$1") (pin "36") (pinfunction "P4.5/A8_36") (pintype "bidirectional"))
    )
    (net (code "73") (name "unconnected-(U$1-P4.6{slash}A7-Pad37)") (class "Default")
      (node (ref "U$1") (pin "37") (pinfunction "P4.6/A7_37") (pintype "bidirectional"))
    )
    (net (code "74") (name "unconnected-(U$1-P4.7{slash}A6-Pad38)") (class "Default")
      (node (ref "U$1") (pin "38") (pinfunction "P4.7/A6_38") (pintype "bidirectional"))
    )
    (net (code "75") (name "unconnected-(U$1-P6.6{slash}TA2.3{slash}UCB3SIMO{slash}UCB3SDA{slash}C1.1-Pad49)") (class "Default")
      (node (ref "U$1") (pin "49") (pinfunction "P6.6/TA2.3/UCB3SIMO/UCB3SDA/C1.1_49") (pintype "bidirectional"))
    )
    (net (code "76") (name "unconnected-(U$1-P7.0{slash}PM_SMCLK{slash}PM_DMAE0-Pad57)") (class "Default")
      (node (ref "U$1") (pin "57") (pinfunction "P7.0/PM_SMCLK/PM_DMAE0_57") (pintype "bidirectional"))
    )
    (net (code "77") (name "unconnected-(U$1-P7.1{slash}PM_C0OUT{slash}PM_TA0CLK-Pad58)") (class "Default")
      (node (ref "U$1") (pin "58") (pinfunction "P7.1/PM_C0OUT/PM_TA0CLK_58") (pintype "bidirectional"))
    )
    (net (code "78") (name "unconnected-(U$1-P7.2{slash}PM_C1OUT{slash}PM_TA1CLK-Pad59)") (class "Default")
      (node (ref "U$1") (pin "59") (pinfunction "P7.2/PM_C1OUT/PM_TA1CLK_59") (pintype "bidirectional"))
    )
    (net (code "79") (name "unconnected-(U$1-P7.3{slash}PM_TA0.0-Pad60)") (class "Default")
      (node (ref "U$1") (pin "60") (pinfunction "P7.3/PM_TA0.0_60") (pintype "bidirectional"))
    )
    (net (code "80") (name "unconnected-(U$1-P8.1{slash}UCB3CLK{slash}TA2.0{slash}C0.0-Pad18)") (class "Default")
      (node (ref "U$1") (pin "18") (pinfunction "P8.1/UCB3CLK/TA2.0/C0.0_18") (pintype "bidirectional"))
    )
    (net (code "81") (name "unconnected-(U$1-PJ.0{slash}LFXIN-Pad28)") (class "Default")
      (node (ref "U$1") (pin "28") (pinfunction "PJ.0/LFXIN_28") (pintype "bidirectional"))
    )
    (net (code "82") (name "unconnected-(U$1-PJ.1{slash}LFXOUT-Pad29)") (class "Default")
      (node (ref "U$1") (pin "29") (pinfunction "PJ.1/LFXOUT_29") (pintype "bidirectional"))
    )
    (net (code "83") (name "unconnected-(U$1-VSW-Pad11)") (class "Default")
      (node (ref "U$1") (pin "11") (pinfunction "VSW_11") (pintype "bidirectional"))
    )
    (net (code "84") (name "unconnected-(U1A-CBUS2-Pad10)") (class "Default")
      (node (ref "U1") (pin "10") (pinfunction "CBUS2_10") (pintype "passive"))
    )
    (net (code "85") (name "unconnected-(U1A-CBUS3-Pad11)") (class "Default")
      (node (ref "U1") (pin "11") (pinfunction "CBUS3_11") (pintype "passive"))
    )
    (net (code "86") (name "unconnected-(U1A-CBUS4-Pad9)") (class "Default")
      (node (ref "U1") (pin "9") (pinfunction "CBUS4_9") (pintype "passive"))
    )
    (net (code "87") (name "unconnected-(U1A-CTS-Pad8)") (class "Default")
      (node (ref "U1") (pin "8") (pinfunction "CTS_8") (pintype "passive"))
    )
    (net (code "88") (name "unconnected-(U1A-DCD-Pad7)") (class "Default")
      (node (ref "U1") (pin "7") (pinfunction "DCD_7") (pintype "passive"))
    )
    (net (code "89") (name "unconnected-(U1A-DSR-Pad6)") (class "Default")
      (node (ref "U1") (pin "6") (pinfunction "DSR_6") (pintype "passive"))
    )
    (net (code "90") (name "unconnected-(U1A-EPAD-Pad33)") (class "Default")
      (node (ref "U1") (pin "33") (pinfunction "EPAD_33") (pintype "passive"))
    )
    (net (code "91") (name "unconnected-(U1A-OSCI-Pad27)") (class "Default")
      (node (ref "U1") (pin "27") (pinfunction "OSCI_27") (pintype "passive"))
    )
    (net (code "92") (name "unconnected-(U1A-OSCO-Pad28)") (class "Default")
      (node (ref "U1") (pin "28") (pinfunction "OSCO_28") (pintype "passive"))
    )
    (net (code "93") (name "unconnected-(U1A-RESET-Pad18)") (class "Default")
      (node (ref "U1") (pin "18") (pinfunction "RESET_18") (pintype "passive"))
    )
    (net (code "94") (name "unconnected-(U1A-RI-Pad3)") (class "Default")
      (node (ref "U1") (pin "3") (pinfunction "RI_3") (pintype "passive"))
    )
    (net (code "95") (name "unconnected-(U1A-RTS-Pad32)") (class "Default")
      (node (ref "U1") (pin "32") (pinfunction "RTS_32") (pintype "passive"))
    )
    (net (code "96") (name "unconnected-(U1B-NC-Pad29)") (class "Default")
      (node (ref "U1") (pin "29") (pinfunction "NC_29") (pintype "passive"))
    )
    (net (code "97") (name "unconnected-(U1B-NC_2-Pad5)") (class "Default")
      (node (ref "U1") (pin "5") (pinfunction "NC_2_5") (pintype "passive"))
    )
    (net (code "98") (name "unconnected-(U1B-NC_3-Pad12)") (class "Default")
      (node (ref "U1") (pin "12") (pinfunction "NC_3_12") (pintype "passive"))
    )
    (net (code "99") (name "unconnected-(U1B-NC_4-Pad13)") (class "Default")
      (node (ref "U1") (pin "13") (pinfunction "NC_4_13") (pintype "passive"))
    )
    (net (code "100") (name "unconnected-(U1B-NC_5-Pad23)") (class "Default")
      (node (ref "U1") (pin "23") (pinfunction "NC_5_23") (pintype "passive"))
    )
    (net (code "101") (name "unconnected-(U1B-NC_6-Pad25)") (class "Default")
      (node (ref "U1") (pin "25") (pinfunction "NC_6_25") (pintype "passive"))
    )
    (net (code "102") (name "unconnected-(U2-NC-Pad4)") (class "Default")
      (node (ref "U2") (pin "4") (pinfunction "NC_4") (pintype "no_connect"))
    )
  )
)
